# XbeeOnBoard.net
KiCad netlist of a schematic drawn in EAGLE
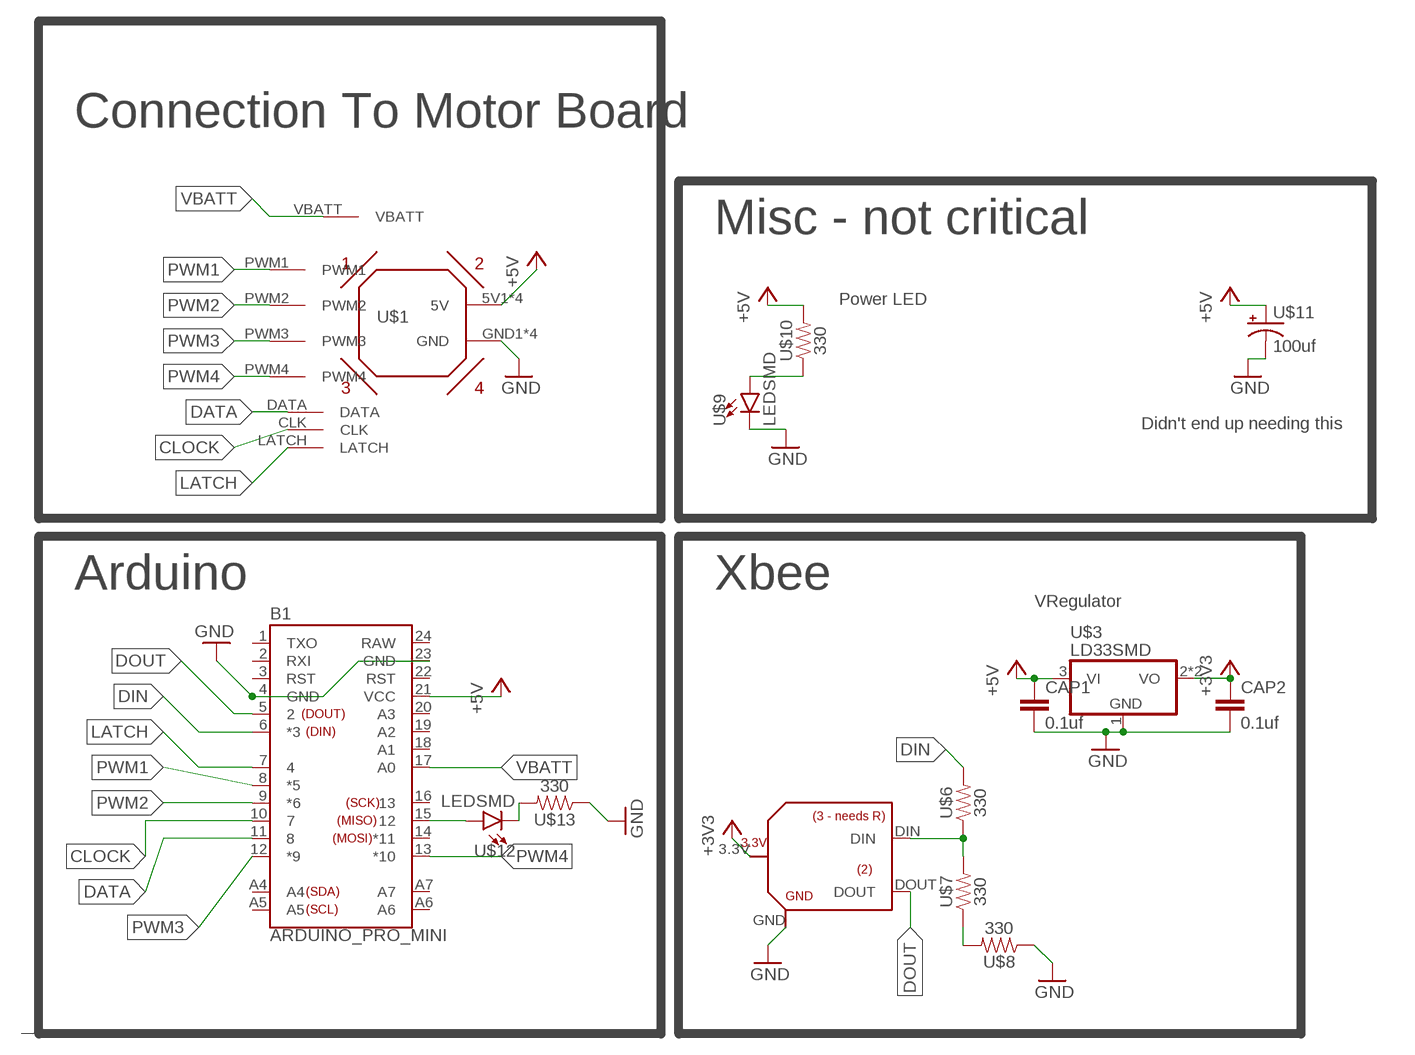
[diagram p0: schematic, sheet 1]

(export (version "E")
  (design (tool "Eeschema 10.0.6"))
  (components
    (comp (ref "B1")
      (value "ARDUINO_PRO_MINI")
      (footprint "eagle-import:ARDUINO_PRO_MINI")
      (libsource (lib "eagle-import") (part "ARDUINO_PRO_MINI"))
    )
    (comp (ref "CAP1")
      (value "0.1uf")
      (footprint "eagle-import:C1206")
      (libsource (lib "eagle-import") (part "CAP_SMCAP"))
    )
    (comp (ref "CAP2")
      (value "0.1uf")
      (footprint "eagle-import:C1206")
      (libsource (lib "eagle-import") (part "CAP_SMCAP"))
    )
    (comp (ref "U$1")
      (value "OMNIBOARD")
      (footprint "eagle-import:OMNIBOARD")
      (libsource (lib "eagle-import") (part "OMNIBOARD"))
    )
    (comp (ref "U$2")
      (value "XBEE_BOUT")
      (footprint "eagle-import:XBEE_BOUT")
      (libsource (lib "eagle-import") (part "XBEE_BOUT"))
    )
    (comp (ref "U$3")
      (value "LD33SMD")
      (footprint "eagle-import:SOT223")
      (libsource (lib "eagle-import") (part "LD33SMD"))
    )
    (comp (ref "U$6")
      (value "330")
      (footprint "eagle-import:R1206")
      (libsource (lib "eagle-import") (part "RESISTORSMD"))
    )
    (comp (ref "U$7")
      (value "330")
      (footprint "eagle-import:R1206")
      (libsource (lib "eagle-import") (part "RESISTORSMD"))
    )
    (comp (ref "U$8")
      (value "330")
      (footprint "eagle-import:R1206")
      (libsource (lib "eagle-import") (part "RESISTORSMD"))
    )
    (comp (ref "U$9")
      (value "LEDSMD")
      (footprint "eagle-import:LED_SMD")
      (libsource (lib "eagle-import") (part "LEDSMD"))
    )
    (comp (ref "U$10")
      (value "330")
      (footprint "eagle-import:R1206")
      (libsource (lib "eagle-import") (part "RESISTORSMD"))
    )
    (comp (ref "U$11")
      (value "100uf")
      (footprint "eagle-import:CAP_E")
      (libsource (lib "eagle-import") (part "CAP_EMED"))
    )
    (comp (ref "U$12")
      (value "LEDSMD")
      (footprint "eagle-import:LED_SMD")
      (libsource (lib "eagle-import") (part "LEDSMD"))
    )
    (comp (ref "U$13")
      (value "330")
      (footprint "eagle-import:R1206")
      (libsource (lib "eagle-import") (part "RESISTORSMD"))
    )
  )
  (nets
    (net (code "1") (name "+3V3") (class "Default")
      (node (ref "CAP2") (pin "1") (pinfunction "1_1") (pintype "passive"))
      (node (ref "U$2") (pin "3.3V") (pinfunction "3.3V_3.3V") (pintype "bidirectional"))
      (node (ref "U$3") (pin "2") (pinfunction "VO_2") (pintype "passive"))
      (node (ref "U$3") (pin "4") (pinfunction "VO_4") (pintype "passive"))
    )
    (net (code "2") (name "+5V") (class "Default")
      (node (ref "B1") (pin "21") (pinfunction "VCC_21") (pintype "power_in"))
      (node (ref "CAP1") (pin "1") (pinfunction "1_1") (pintype "passive"))
      (node (ref "U$1") (pin "5V1") (pinfunction "5V_5V1") (pintype "passive"))
      (node (ref "U$1") (pin "5V2") (pinfunction "5V_5V2") (pintype "passive"))
      (node (ref "U$1") (pin "5V3") (pinfunction "5V_5V3") (pintype "passive"))
      (node (ref "U$1") (pin "5V4") (pinfunction "5V_5V4") (pintype "passive"))
      (node (ref "U$10") (pin "2") (pinfunction "2_2") (pintype "passive"))
      (node (ref "U$11") (pin "+") (pinfunction "+_+") (pintype "passive"))
      (node (ref "U$3") (pin "3") (pinfunction "VI_3") (pintype "input"))
    )
    (net (code "3") (name "/RAW") (class "Default")
      (node (ref "B1") (pin "24") (pinfunction "RAW_24") (pintype "power_in"))
    )
    (net (code "4") (name "CLOCK") (class "Default")
      (node (ref "B1") (pin "10") (pinfunction "7_10") (pintype "bidirectional"))
      (node (ref "U$1") (pin "CLK") (pinfunction "CLK_CLK") (pintype "passive"))
    )
    (net (code "5") (name "DATA") (class "Default")
      (node (ref "B1") (pin "11") (pinfunction "8_11") (pintype "bidirectional"))
      (node (ref "U$1") (pin "DATA") (pinfunction "DATA_DATA") (pintype "passive"))
    )
    (net (code "6") (name "DIN") (class "Default")
      (node (ref "B1") (pin "6") (pinfunction "*3_6") (pintype "bidirectional"))
      (node (ref "U$6") (pin "2") (pinfunction "2_2") (pintype "passive"))
    )
    (net (code "7") (name "DOUT") (class "Default")
      (node (ref "B1") (pin "5") (pinfunction "2_5") (pintype "bidirectional"))
      (node (ref "U$2") (pin "DOUT") (pinfunction "DOUT_DOUT") (pintype "bidirectional"))
    )
    (net (code "8") (name "GND") (class "Default")
      (node (ref "B1") (pin "23") (pinfunction "GND_23") (pintype "power_in"))
      (node (ref "B1") (pin "4") (pinfunction "GND_4") (pintype "power_in"))
      (node (ref "CAP1") (pin "2") (pinfunction "2_2") (pintype "passive"))
      (node (ref "CAP2") (pin "2") (pinfunction "2_2") (pintype "passive"))
      (node (ref "U$1") (pin "GND1") (pinfunction "GND_GND1") (pintype "passive"))
      (node (ref "U$1") (pin "GND2") (pinfunction "GND_GND2") (pintype "passive"))
      (node (ref "U$1") (pin "GND3") (pinfunction "GND_GND3") (pintype "passive"))
      (node (ref "U$1") (pin "GND4") (pinfunction "GND_GND4") (pintype "passive"))
      (node (ref "U$11") (pin "-") (pinfunction "-_-") (pintype "passive"))
      (node (ref "U$13") (pin "1") (pinfunction "1_1") (pintype "passive"))
      (node (ref "U$2") (pin "GND") (pinfunction "GND_GND") (pintype "bidirectional"))
      (node (ref "U$3") (pin "1") (pinfunction "GND_1") (pintype "passive"))
      (node (ref "U$8") (pin "1") (pinfunction "1_1") (pintype "passive"))
      (node (ref "U$9") (pin "C") (pinfunction "C_C") (pintype "passive"))
    )
    (net (code "9") (name "LATCH") (class "Default")
      (node (ref "B1") (pin "7") (pinfunction "4_7") (pintype "bidirectional"))
      (node (ref "U$1") (pin "LATCH") (pinfunction "LATCH_LATCH") (pintype "passive"))
    )
    (net (code "10") (name "Net-(B1-12)") (class "Default")
      (node (ref "B1") (pin "15") (pinfunction "12_15") (pintype "bidirectional"))
      (node (ref "U$12") (pin "A") (pinfunction "A_A") (pintype "passive"))
    )
    (net (code "11") (name "Net-(U$2-PadDIN)") (class "Default")
      (node (ref "U$2") (pin "DIN") (pinfunction "DIN_DIN") (pintype "bidirectional"))
      (node (ref "U$6") (pin "1") (pinfunction "1_1") (pintype "passive"))
      (node (ref "U$7") (pin "2") (pinfunction "2_2") (pintype "passive"))
    )
    (net (code "12") (name "Net-(U$7-Pad1)") (class "Default")
      (node (ref "U$7") (pin "1") (pinfunction "1_1") (pintype "passive"))
      (node (ref "U$8") (pin "2") (pinfunction "2_2") (pintype "passive"))
    )
    (net (code "13") (name "Net-(U$10-Pad1)") (class "Default")
      (node (ref "U$10") (pin "1") (pinfunction "1_1") (pintype "passive"))
      (node (ref "U$9") (pin "A") (pinfunction "A_A") (pintype "passive"))
    )
    (net (code "14") (name "Net-(U$12-PadC)") (class "Default")
      (node (ref "U$12") (pin "C") (pinfunction "C_C") (pintype "passive"))
      (node (ref "U$13") (pin "2") (pinfunction "2_2") (pintype "passive"))
    )
    (net (code "15") (name "PWM1") (class "Default")
      (node (ref "B1") (pin "8") (pinfunction "*5_8") (pintype "bidirectional"))
      (node (ref "U$1") (pin "PWM1") (pinfunction "PWM1_PWM1") (pintype "passive"))
    )
    (net (code "16") (name "PWM2") (class "Default")
      (node (ref "B1") (pin "9") (pinfunction "*6_9") (pintype "bidirectional"))
      (node (ref "U$1") (pin "PWM2") (pinfunction "PWM2_PWM2") (pintype "passive"))
    )
    (net (code "17") (name "PWM3") (class "Default")
      (node (ref "B1") (pin "12") (pinfunction "*9_12") (pintype "bidirectional"))
      (node (ref "U$1") (pin "PWM3") (pinfunction "PWM3_PWM3") (pintype "passive"))
    )
    (net (code "18") (name "PWM4") (class "Default")
      (node (ref "B1") (pin "13") (pinfunction "*10_13") (pintype "bidirectional"))
      (node (ref "U$1") (pin "PWM4") (pinfunction "PWM4_PWM4") (pintype "passive"))
    )
    (net (code "19") (name "VBATT") (class "Default")
      (node (ref "B1") (pin "17") (pinfunction "A0_17") (pintype "bidirectional"))
      (node (ref "U$1") (pin "VBATT") (pinfunction "VBATT_VBATT") (pintype "passive"))
    )
    (net (code "20") (name "unconnected-(B1-*11-Pad14)") (class "Default")
      (node (ref "B1") (pin "14") (pinfunction "*11_14") (pintype "bidirectional"))
    )
    (net (code "21") (name "unconnected-(B1-13-Pad16)") (class "Default")
      (node (ref "B1") (pin "16") (pinfunction "13_16") (pintype "bidirectional"))
    )
    (net (code "22") (name "unconnected-(B1-A1-Pad18)") (class "Default")
      (node (ref "B1") (pin "18") (pinfunction "A1_18") (pintype "bidirectional"))
    )
    (net (code "23") (name "unconnected-(B1-A2-Pad19)") (class "Default")
      (node (ref "B1") (pin "19") (pinfunction "A2_19") (pintype "bidirectional"))
    )
    (net (code "24") (name "unconnected-(B1-A3-Pad20)") (class "Default")
      (node (ref "B1") (pin "20") (pinfunction "A3_20") (pintype "bidirectional"))
    )
    (net (code "25") (name "unconnected-(B1-PadA4)") (class "Default")
      (node (ref "B1") (pin "A4") (pinfunction "A4_A4") (pintype "bidirectional"))
    )
    (net (code "26") (name "unconnected-(B1-PadA5)") (class "Default")
      (node (ref "B1") (pin "A5") (pinfunction "A5_A5") (pintype "bidirectional"))
    )
    (net (code "27") (name "unconnected-(B1-PadA6)") (class "Default")
      (node (ref "B1") (pin "A6") (pinfunction "A6_A6") (pintype "bidirectional"))
    )
    (net (code "28") (name "unconnected-(B1-PadA7)") (class "Default")
      (node (ref "B1") (pin "A7") (pinfunction "A7_A7") (pintype "bidirectional"))
    )
    (net (code "29") (name "unconnected-(B1-RST-Pad3)") (class "Default")
      (node (ref "B1") (pin "3") (pinfunction "RST_3") (pintype "bidirectional"))
    )
    (net (code "30") (name "unconnected-(B1-RST-Pad22)") (class "Default")
      (node (ref "B1") (pin "22") (pinfunction "RST_22") (pintype "bidirectional"))
    )
    (net (code "31") (name "unconnected-(B1-RXI-Pad2)") (class "Default")
      (node (ref "B1") (pin "2") (pinfunction "RXI_2") (pintype "bidirectional"))
    )
    (net (code "32") (name "unconnected-(B1-TXO-Pad1)") (class "Default")
      (node (ref "B1") (pin "1") (pinfunction "TXO_1") (pintype "bidirectional"))
    )
  )
)
